# xerife.net
KiCad netlist of a schematic drawn in EAGLE
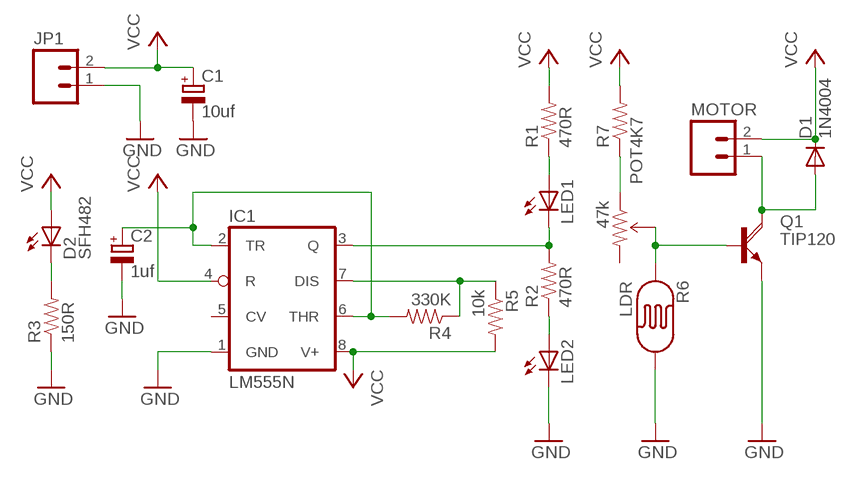
[diagram p0: schematic, sheet 1]

(export (version "E")
  (design (tool "Eeschema 10.0.6"))
  (components
    (comp (ref "C1")
      (value "10uf")
      (footprint "eagle-import:E5-5")
      (libsource (lib "eagle-import") (part "CPOL-EUE5-5"))
    )
    (comp (ref "C2")
      (value "1uf")
      (footprint "eagle-import:E5-5")
      (libsource (lib "eagle-import") (part "CPOL-EUE5-5"))
    )
    (comp (ref "D1")
      (value "1N4004")
      (footprint "eagle-import:DO41-10")
      (libsource (lib "eagle-import") (part "1N4004"))
    )
    (comp (ref "D2")
      (value "SFH482")
      (footprint "eagle-import:SFH482")
      (libsource (lib "eagle-import") (part "SFH482"))
    )
    (comp (ref "IC1")
      (value "LM555N")
      (footprint "eagle-import:DIL08-ROUND")
      (libsource (lib "eagle-import") (part "555NLM"))
    )
    (comp (ref "JP1")
      (value "M025MM")
      (footprint "eagle-import:SCREWTERMINAL-5MM-2")
      (libsource (lib "eagle-import") (part "M025MM"))
    )
    (comp (ref "LED1")
      (value "LED5MM")
      (footprint "eagle-import:LED5MM")
      (libsource (lib "eagle-import") (part "LED5MM"))
    )
    (comp (ref "LED2")
      (value "LED5MM")
      (footprint "eagle-import:LED5MM")
      (libsource (lib "eagle-import") (part "LED5MM"))
    )
    (comp (ref "MOTOR")
      (value "M021X02_NO_SILK")
      (footprint "eagle-import:1X02_NO_SILK")
      (libsource (lib "eagle-import") (part "M021X02_NO_SILK"))
    )
    (comp (ref "POT")
      (value "47k")
      (footprint "eagle-import:TRIM_POT_PTH")
      (libsource (lib "eagle-import") (part "TRIMPOTPTH"))
    )
    (comp (ref "Q1")
      (value "TIP120")
      (footprint "eagle-import:TO220AH")
      (libsource (lib "eagle-import") (part "TIP120"))
    )
    (comp (ref "R1")
      (value "470R")
      (footprint "eagle-import:AXIAL-0.4")
      (libsource (lib "eagle-import") (part "RESISTORPTH-1/4W"))
    )
    (comp (ref "R2")
      (value "470R")
      (footprint "eagle-import:AXIAL-0.4")
      (libsource (lib "eagle-import") (part "RESISTORPTH-1/4W"))
    )
    (comp (ref "R3")
      (value "150R")
      (footprint "eagle-import:AXIAL-0.4")
      (libsource (lib "eagle-import") (part "RESISTORPTH-1/4W"))
    )
    (comp (ref "R4")
      (value "330K")
      (footprint "eagle-import:AXIAL-0.4")
      (libsource (lib "eagle-import") (part "RESISTORPTH-1/4W"))
    )
    (comp (ref "R5")
      (value "10k")
      (footprint "eagle-import:AXIAL-0.4")
      (libsource (lib "eagle-import") (part "RESISTORPTH-1/4W"))
    )
    (comp (ref "R6")
      (value "LDR")
      (footprint "eagle-import:PHOTOCELL-KIT")
      (libsource (lib "eagle-import") (part "PHOTOCELLPTH-KIT"))
    )
    (comp (ref "R7")
      (value "4K7")
      (footprint "eagle-import:AXIAL-0.4")
      (libsource (lib "eagle-import") (part "RESISTORPTH-1/4W"))
    )
  )
  (nets
    (net (code "1") (name "GND") (class "Default")
      (node (ref "C1") (pin "-") (pinfunction "-_-") (pintype "passive"))
      (node (ref "C2") (pin "-") (pinfunction "-_-") (pintype "passive"))
      (node (ref "IC1") (pin "1") (pinfunction "GND_1") (pintype "power_in"))
      (node (ref "JP1") (pin "1") (pinfunction "1_1") (pintype "passive"))
      (node (ref "LED2") (pin "K") (pinfunction "C_K") (pintype "passive"))
      (node (ref "Q1") (pin "E") (pinfunction "E_E") (pintype "passive"))
      (node (ref "R3") (pin "P$1") (pinfunction "1_P$1") (pintype "passive"))
      (node (ref "R6") (pin "2") (pinfunction "P$2_2") (pintype "bidirectional"))
    )
    (net (code "2") (name "Net-(D1-PadA)") (class "Default")
      (node (ref "D1") (pin "A") (pinfunction "A_A") (pintype "passive"))
      (node (ref "MOTOR") (pin "1") (pinfunction "1_1") (pintype "passive"))
      (node (ref "Q1") (pin "C") (pinfunction "C_C") (pintype "passive"))
    )
    (net (code "3") (name "Net-(D2-C)") (class "Default")
      (node (ref "D2") (pin "K") (pinfunction "C_K") (pintype "passive"))
      (node (ref "R3") (pin "P$2") (pinfunction "2_P$2") (pintype "passive"))
    )
    (net (code "4") (name "Net-(IC1-DIS)") (class "Default")
      (node (ref "IC1") (pin "7") (pinfunction "DIS_7") (pintype "input"))
      (node (ref "R4") (pin "P$1") (pinfunction "1_P$1") (pintype "passive"))
      (node (ref "R5") (pin "P$1") (pinfunction "1_P$1") (pintype "passive"))
    )
    (net (code "5") (name "Net-(IC1-Q)") (class "Default")
      (node (ref "IC1") (pin "3") (pinfunction "Q_3") (pintype "output"))
      (node (ref "LED1") (pin "K") (pinfunction "C_K") (pintype "passive"))
      (node (ref "R2") (pin "P$2") (pinfunction "2_P$2") (pintype "passive"))
    )
    (net (code "6") (name "Net-(IC1-THR)") (class "Default")
      (node (ref "C2") (pin "+") (pinfunction "+_+") (pintype "passive"))
      (node (ref "IC1") (pin "2") (pinfunction "TR_2") (pintype "input"))
      (node (ref "IC1") (pin "6") (pinfunction "THR_6") (pintype "input"))
      (node (ref "R4") (pin "P$2") (pinfunction "2_P$2") (pintype "passive"))
    )
    (net (code "7") (name "Net-(POT-CCW)") (class "Default")
      (node (ref "POT") (pin "1") (pinfunction "CCW_1") (pintype "passive"))
      (node (ref "R7") (pin "P$1") (pinfunction "1_P$1") (pintype "passive"))
    )
    (net (code "8") (name "Net-(POT-WIPER)") (class "Default")
      (node (ref "POT") (pin "2") (pinfunction "WIPER_2") (pintype "passive"))
      (node (ref "Q1") (pin "B") (pinfunction "B_B") (pintype "passive"))
      (node (ref "R6") (pin "1") (pinfunction "P$1_1") (pintype "bidirectional"))
    )
    (net (code "9") (name "Net-(R1-1)") (class "Default")
      (node (ref "LED1") (pin "A") (pinfunction "A_A") (pintype "passive"))
      (node (ref "R1") (pin "P$1") (pinfunction "1_P$1") (pintype "passive"))
    )
    (net (code "10") (name "Net-(R2-1)") (class "Default")
      (node (ref "LED2") (pin "A") (pinfunction "A_A") (pintype "passive"))
      (node (ref "R2") (pin "P$1") (pinfunction "1_P$1") (pintype "passive"))
    )
    (net (code "11") (name "VCC") (class "Default")
      (node (ref "C1") (pin "+") (pinfunction "+_+") (pintype "passive"))
      (node (ref "D1") (pin "C") (pinfunction "C_C") (pintype "passive"))
      (node (ref "D2") (pin "A") (pinfunction "A_A") (pintype "passive"))
      (node (ref "IC1") (pin "4") (pinfunction "R_4") (pintype "input"))
      (node (ref "IC1") (pin "8") (pinfunction "V+_8") (pintype "power_in"))
      (node (ref "JP1") (pin "2") (pinfunction "2_2") (pintype "passive"))
      (node (ref "MOTOR") (pin "2") (pinfunction "2_2") (pintype "passive"))
      (node (ref "R1") (pin "P$2") (pinfunction "2_P$2") (pintype "passive"))
      (node (ref "R5") (pin "P$2") (pinfunction "2_P$2") (pintype "passive"))
      (node (ref "R7") (pin "P$2") (pinfunction "2_P$2") (pintype "passive"))
    )
    (net (code "12") (name "unconnected-(IC1-CV-Pad5)") (class "Default")
      (node (ref "IC1") (pin "5") (pinfunction "CV_5") (pintype "input"))
    )
    (net (code "13") (name "unconnected-(POT-CW-Pad3)") (class "Default")
      (node (ref "POT") (pin "3") (pinfunction "CW_3") (pintype "passive"))
    )
  )
)
